# LightRelay.net
KiCad netlist of a schematic drawn in Altium Designer
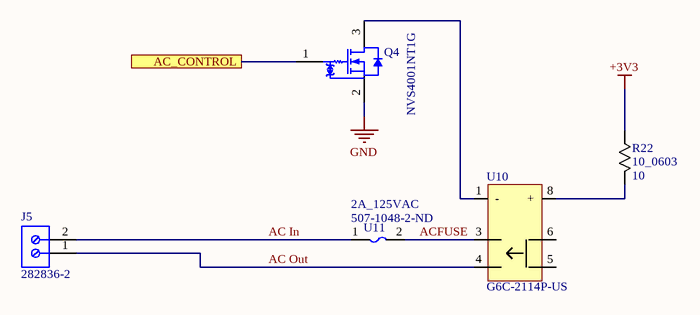
[diagram p0: LightRelay.SchDoc]

(export (version "E")
  (design (tool "Eeschema 10.0.6"))
  (components
    (comp (ref "J5")
      (value "282836-2")
      (footprint "TECO-282836-2_V")
      (description "Female Header, Pitch 5 mm, 1 x 2 Position, Height 10 mm, Tail Length 3.5 mm, Rohs, Bulk")
      (fields (field (name "VOLTAGE") "300V"))
      (libsource (lib "TE Terminal Blocks and Strips") (part "282836-2"))
    )
    (comp (ref "Q4")
      (value "NVS4001NT1G")
      (footprint "ONSC-SC-70-3-419-04_V")
      (description "Small Signal MOSFET, 30 V, 270 mA, N-Channel, 3-Pin SC70, Pb-Free, Tape and Reel")
      (fields (field (name "MANUFACTURER") "On Semiconductor"))
      (libsource (lib "ON Semi MOSFETs") (part "NVS4001NT1G"))
    )
    (comp (ref "R22")
      (value "10_0603")
      (footprint "0603")
      (fields
        (field (name "MANUFACTURER") "Vishay")
        (field (name "MANUFACTURER PART NUMBER") "CRCW060310R0FKEA")
        (field (name "TOLERANCE") "1%")
        (field (name "RESISTANCE") "10")
      )
      (libsource (lib "Resistors") (part "10_0603"))
    )
    (comp (ref "U10")
      (value "G6C-2114P-US")
      (footprint "G6C-2114P-US")
      (description "RELAY GENERAL PURPOSE DPST 8A 3V 67mA coil drive 45ohm coil resistance")
      (libsource (lib "MiscComponents") (part "G6C-2114P-US"))
    )
    (comp (ref "U11")
      (value "2A_125VAC")
      (footprint "2410")
      (fields
        (field (name "MANUFACTURER") "Bel")
        (field (name "MANUFACTURER PART NUMBER") "SSQ2")
        (field (name "SUPPLIER PART NUMBER 1") "507-1048-2-ND")
      )
      (libsource (lib "MiscComponents") (part "2A_125VAC"))
    )
  )
  (nets
    (net (code "1") (name "+3V3") (class "Default")
      (node (ref "R22") (pin "2") (pinfunction "2_2") (pintype "passive"))
    )
    (net (code "2") (name "/AC In") (class "Default")
      (node (ref "J5") (pin "2") (pinfunction "2_2") (pintype "passive"))
      (node (ref "U11") (pin "1") (pinfunction "1_1") (pintype "passive"))
    )
    (net (code "3") (name "/AC Out") (class "Default")
      (node (ref "J5") (pin "1") (pinfunction "1_1") (pintype "passive"))
      (node (ref "U10") (pin "4") (pintype "passive"))
    )
    (net (code "4") (name "/ACFUSE") (class "Default")
      (node (ref "U10") (pin "3") (pintype "passive"))
      (node (ref "U11") (pin "2") (pinfunction "2_2") (pintype "passive"))
    )
    (net (code "5") (name "/AC_CONTROL") (class "Default")
      (node (ref "Q4") (pin "1") (pinfunction "G_1") (pintype "passive"))
    )
    (net (code "6") (name "GND") (class "Default")
      (node (ref "Q4") (pin "2") (pinfunction "S_2") (pintype "passive"))
    )
    (net (code "7") (name "Net-(Q4-D)") (class "Default")
      (node (ref "Q4") (pin "3") (pinfunction "D_3") (pintype "passive"))
      (node (ref "U10") (pin "1") (pinfunction "-_1") (pintype "passive"))
    )
    (net (code "8") (name "Net-(U10-+)") (class "Default")
      (node (ref "R22") (pin "1") (pinfunction "1_1") (pintype "passive"))
      (node (ref "U10") (pin "8") (pinfunction "+_8") (pintype "passive"))
    )
    (net (code "9") (name "unconnected-(U10-Pad5)") (class "Default")
      (node (ref "U10") (pin "5") (pintype "passive"))
    )
    (net (code "10") (name "unconnected-(U10-Pad6)") (class "Default")
      (node (ref "U10") (pin "6") (pintype "passive"))
    )
  )
)
